# SensWear_Debug.net
KiCad netlist of a schematic drawn in Altium Designer
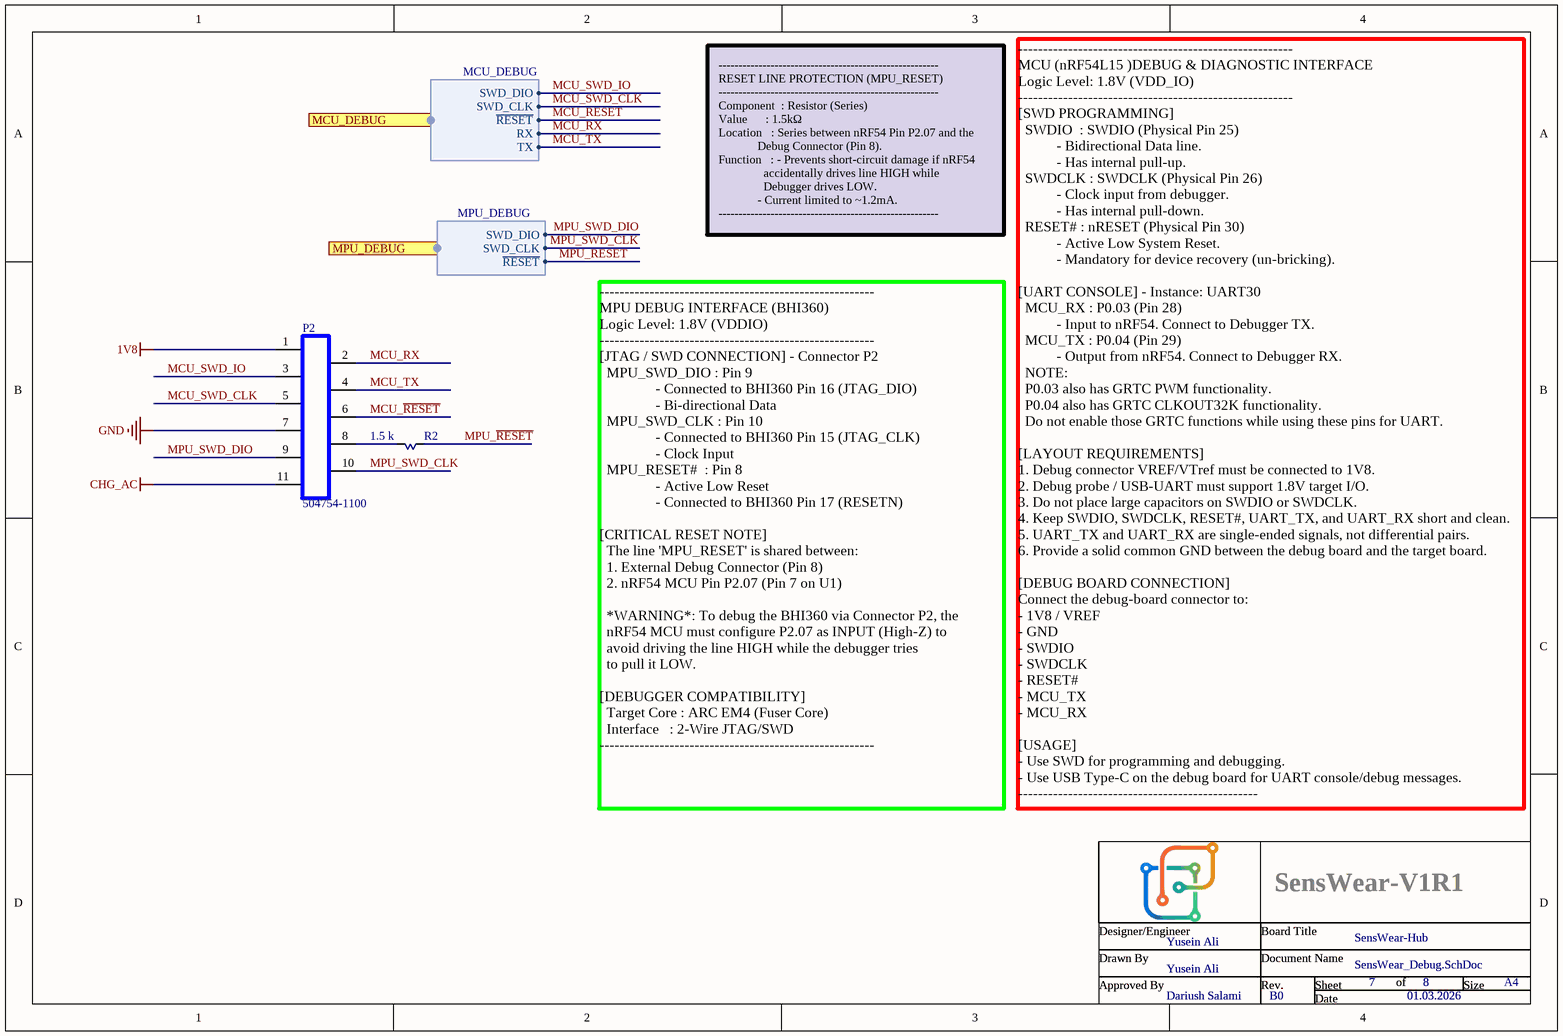
[diagram p0: SensWear_Debug.SchDoc]

(export (version "E")
  (design (tool "Eeschema 10.0.6"))
  (components
    (comp (ref "P2")
      (value "504754-1100")
      (footprint "5047541100__3")
      (description "Conn FFC/FPC Connector SKT 11 POS 0.3mm Solder RA SMD Easy-On™ T/R")
      (fields (field (name "MANUFACTURER") "Molex") (field (name "CHECKED") "FALSE"))
      (libsource (lib "SensWearComponents") (part "504754-1100"))
    )
    (comp (ref "R2")
      (value "1.5 k")
      (footprint "RESC1005X04N")
      (description "RES SMD 1.5K OHM 1% 1/10W 0402")
      (fields
        (field (name "MANUFACTURER") "Panasonic Electronic Components")
        (field (name "MANUFACTURER PART NUMBER") "ERJ-2RKF1501X")
      )
      (libsource (lib "SensWearComponents") (part "ERJ-2RKF1501X"))
    )
  )
  (nets
    (net (code "3") (name "/MCU_RX") (class "Default")
      (node (ref "P2") (pin "2") (pinfunction "2_2") (pintype "passive"))
    )
    (net (code "4") (name "/MCU_SWD_CLK") (class "Default")
      (node (ref "P2") (pin "5") (pinfunction "5_5") (pintype "passive"))
    )
    (net (code "5") (name "/MCU_SWD_IO") (class "Default")
      (node (ref "P2") (pin "3") (pinfunction "3_3") (pintype "passive"))
    )
    (net (code "6") (name "/MCU_TX") (class "Default")
      (node (ref "P2") (pin "4") (pinfunction "4_4") (pintype "passive"))
    )
    (net (code "7") (name "/MCU_~{RESET}") (class "Default")
      (node (ref "P2") (pin "6") (pinfunction "6_6") (pintype "passive"))
    )
    (net (code "8") (name "/MPU_SWD_CLK") (class "Default")
      (node (ref "P2") (pin "10") (pinfunction "10_10") (pintype "passive"))
    )
    (net (code "9") (name "/MPU_SWD_DIO") (class "Default")
      (node (ref "P2") (pin "9") (pinfunction "9_9") (pintype "passive"))
    )
    (net (code "10") (name "/MPU_~{RESET}") (class "Default")
      (node (ref "R2") (pin "1") (pinfunction "1_1") (pintype "passive"))
    )
    (net (code "13") (name "1V8") (class "Default")
      (node (ref "P2") (pin "1") (pinfunction "1_1") (pintype "passive"))
    )
    (net (code "14") (name "CHG_AC") (class "Default")
      (node (ref "P2") (pin "11") (pinfunction "11_11") (pintype "passive"))
    )
    (net (code "15") (name "GND") (class "Default")
      (node (ref "P2") (pin "7") (pinfunction "7_7") (pintype "passive"))
    )
    (net (code "16") (name "Net-(P2-Pad8)") (class "Default")
      (node (ref "P2") (pin "8") (pinfunction "8_8") (pintype "passive"))
      (node (ref "R2") (pin "2") (pinfunction "2_2") (pintype "passive"))
    )
  )
)
